# acmon_interface.net
KiCad netlist of a schematic drawn in EAGLE
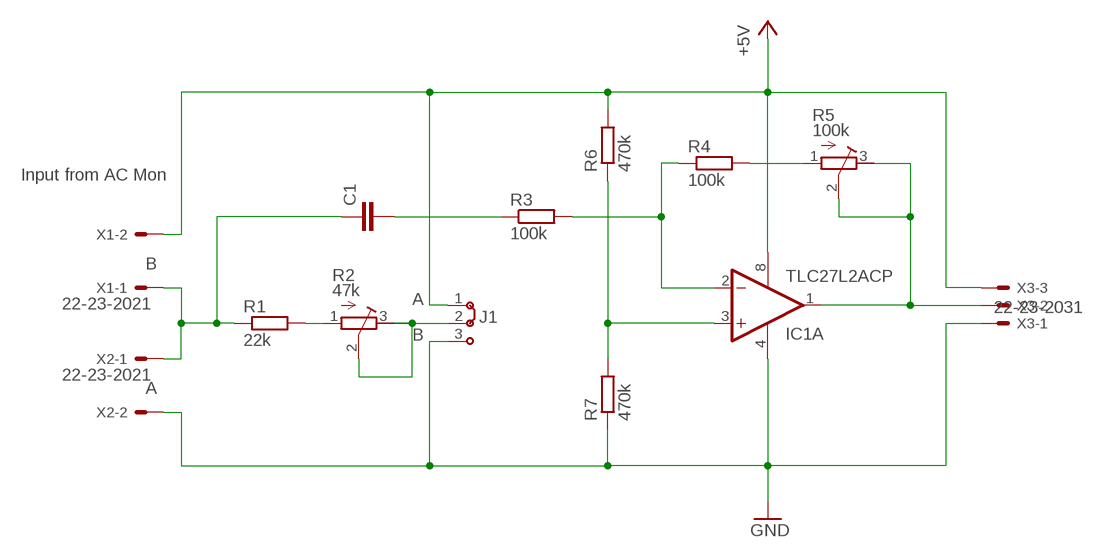
[diagram p0: schematic, sheet 1]

(export (version "E")
  (design (tool "Eeschema 10.0.6"))
  (components
    (comp (ref "C1")
      (value "C-EU050-030X075")
      (footprint "eagle-import:C050-030X075")
      (libsource (lib "eagle-import") (part "C-EU050-030X075"))
    )
    (comp (ref "IC1")
      (value "TLC27L2ACP")
      (footprint "eagle-import:DIL08")
      (libsource (lib "eagle-import") (part "TLC27LP2AC"))
    )
    (comp (ref "J1")
      (value "J2X2MM")
      (footprint "eagle-import:04C")
      (libsource (lib "eagle-import") (part "J2X2MM"))
    )
    (comp (ref "R1")
      (value "22k")
      (footprint "eagle-import:0207_10")
      (libsource (lib "eagle-import") (part "R-EU_0207/10"))
    )
    (comp (ref "R2")
      (value "47k")
      (footprint "eagle-import:RTRIM64Y")
      (libsource (lib "eagle-import") (part "R-TRIMM64Y"))
    )
    (comp (ref "R3")
      (value "100k")
      (footprint "eagle-import:0207_10")
      (libsource (lib "eagle-import") (part "R-EU_0207/10"))
    )
    (comp (ref "R4")
      (value "100k")
      (footprint "eagle-import:0207_10")
      (libsource (lib "eagle-import") (part "R-EU_0207/10"))
    )
    (comp (ref "R5")
      (value "100k")
      (footprint "eagle-import:RTRIM64Y")
      (libsource (lib "eagle-import") (part "R-TRIMM64Y"))
    )
    (comp (ref "R6")
      (value "470k")
      (footprint "eagle-import:0207_10")
      (libsource (lib "eagle-import") (part "R-EU_0207/10"))
    )
    (comp (ref "R7")
      (value "470k")
      (footprint "eagle-import:0207_10")
      (libsource (lib "eagle-import") (part "R-EU_0207/10"))
    )
    (comp (ref "X1")
      (value "22-23-2021")
      (footprint "eagle-import:22-23-2021")
      (fields (field (name "MF") "MOLEX"))
      (libsource (lib "eagle-import") (part "22-23-2021"))
    )
    (comp (ref "X2")
      (value "22-23-2021")
      (footprint "eagle-import:22-23-2021")
      (fields (field (name "MF") "MOLEX"))
      (libsource (lib "eagle-import") (part "22-23-2021"))
    )
    (comp (ref "X3")
      (value "22-23-2031")
      (footprint "eagle-import:22-23-2031")
      (fields (field (name "MF") "MOLEX"))
      (libsource (lib "eagle-import") (part "22-23-2031"))
    )
  )
  (nets
    (net (code "1") (name "+5V") (class "Default")
      (node (ref "IC1") (pin "8") (pinfunction "VDD_8") (pintype "power_in"))
      (node (ref "J1") (pin "1") (pinfunction "1_1") (pintype "passive"))
      (node (ref "R6") (pin "2") (pinfunction "2_2") (pintype "passive"))
      (node (ref "X1") (pin "2") (pinfunction "S_2") (pintype "passive"))
      (node (ref "X3") (pin "3") (pinfunction "S_3") (pintype "passive"))
    )
    (net (code "2") (name "GND") (class "Default")
      (node (ref "IC1") (pin "4") (pinfunction "GND_4") (pintype "power_in"))
      (node (ref "J1") (pin "3") (pinfunction "3_3") (pintype "passive"))
      (node (ref "R7") (pin "1") (pinfunction "1_1") (pintype "passive"))
      (node (ref "X2") (pin "2") (pinfunction "S_2") (pintype "passive"))
      (node (ref "X3") (pin "1") (pinfunction "S_1") (pintype "passive"))
    )
    (net (code "3") (name "Net-(C1-Pad2)") (class "Default")
      (node (ref "C1") (pin "2") (pinfunction "2_2") (pintype "passive"))
      (node (ref "R3") (pin "1") (pinfunction "1_1") (pintype "passive"))
    )
    (net (code "4") (name "Net-(IC1A-+IN)") (class "Default")
      (node (ref "IC1") (pin "3") (pinfunction "+IN_3") (pintype "input"))
      (node (ref "R6") (pin "1") (pinfunction "1_1") (pintype "passive"))
      (node (ref "R7") (pin "2") (pinfunction "2_2") (pintype "passive"))
    )
    (net (code "5") (name "Net-(IC1A--IN)") (class "Default")
      (node (ref "IC1") (pin "2") (pinfunction "-IN_2") (pintype "input"))
      (node (ref "R3") (pin "2") (pinfunction "2_2") (pintype "passive"))
      (node (ref "R4") (pin "1") (pinfunction "1_1") (pintype "passive"))
    )
    (net (code "6") (name "Net-(IC1A-OUT)") (class "Default")
      (node (ref "IC1") (pin "1") (pinfunction "OUT_1") (pintype "output"))
      (node (ref "R5") (pin "2") (pinfunction "S_2") (pintype "passive"))
      (node (ref "R5") (pin "3") (pinfunction "E_3") (pintype "passive"))
      (node (ref "X3") (pin "2") (pinfunction "S_2") (pintype "passive"))
    )
    (net (code "7") (name "Net-(R2-A)") (class "Default")
      (node (ref "R1") (pin "2") (pinfunction "2_2") (pintype "passive"))
      (node (ref "R2") (pin "1") (pinfunction "A_1") (pintype "passive"))
    )
    (net (code "8") (name "Net-(R2-E)") (class "Default")
      (node (ref "J1") (pin "2") (pinfunction "2_2") (pintype "passive"))
      (node (ref "R2") (pin "2") (pinfunction "S_2") (pintype "passive"))
      (node (ref "R2") (pin "3") (pinfunction "E_3") (pintype "passive"))
    )
    (net (code "9") (name "Net-(R5-A)") (class "Default")
      (node (ref "R4") (pin "2") (pinfunction "2_2") (pintype "passive"))
      (node (ref "R5") (pin "1") (pinfunction "A_1") (pintype "passive"))
    )
    (net (code "10") (name "Net-(X1A-S)") (class "Default")
      (node (ref "C1") (pin "1") (pinfunction "1_1") (pintype "passive"))
      (node (ref "R1") (pin "1") (pinfunction "1_1") (pintype "passive"))
      (node (ref "X1") (pin "1") (pinfunction "S_1") (pintype "passive"))
      (node (ref "X2") (pin "1") (pinfunction "S_1") (pintype "passive"))
    )
  )
)
